# board.net
KiCad netlist of a schematic drawn in EAGLE
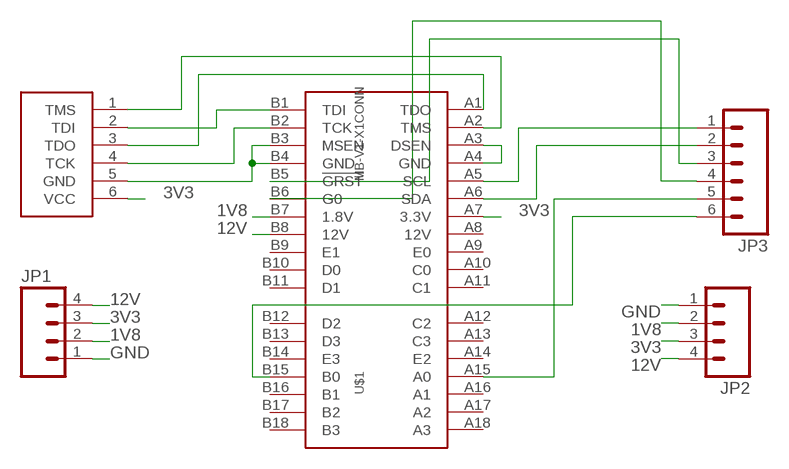
[diagram p0: schematic, sheet 1]

(export (version "E")
  (design (tool "Eeschema 10.0.6"))
  (components
    (comp (ref "JP1")
      (value "M04PTH")
      (footprint "eagle-import:1X04")
      (libsource (lib "eagle-import") (part "M04PTH"))
    )
    (comp (ref "JP2")
      (value "M04PTH")
      (footprint "eagle-import:1X04")
      (libsource (lib "eagle-import") (part "M04PTH"))
    )
    (comp (ref "JP3")
      (value "M06SIP")
      (footprint "eagle-import:1X06")
      (libsource (lib "eagle-import") (part "M06SIP"))
    )
    (comp (ref "U$1")
      (value "MB-V1-X1CONN")
      (footprint "eagle-import:PCIE-X1-CONN")
      (libsource (lib "eagle-import") (part "MB-V1-X1CONN"))
    )
    (comp (ref "U$2")
      (value "JTAGDIGILENT")
      (footprint "eagle-import:1X06")
      (libsource (lib "eagle-import") (part "JTAGDIGILENT"))
    )
  )
  (nets
    (net (code "1") (name "/1V8") (class "Default")
      (node (ref "JP1") (pin "2") (pinfunction "2_2") (pintype "passive"))
      (node (ref "JP2") (pin "2") (pinfunction "2_2") (pintype "passive"))
      (node (ref "U$1") (pin "B7") (pinfunction "1.8V_B7") (pintype "bidirectional"))
    )
    (net (code "2") (name "/3V3") (class "Default")
      (node (ref "JP1") (pin "3") (pinfunction "3_3") (pintype "passive"))
      (node (ref "JP2") (pin "3") (pinfunction "3_3") (pintype "passive"))
      (node (ref "U$1") (pin "A7") (pinfunction "3.3V_A7") (pintype "bidirectional"))
      (node (ref "U$2") (pin "6") (pinfunction "VCC_6") (pintype "bidirectional"))
    )
    (net (code "3") (name "/12V") (class "Default")
      (node (ref "JP1") (pin "4") (pinfunction "4_4") (pintype "passive"))
      (node (ref "JP2") (pin "4") (pinfunction "4_4") (pintype "passive"))
      (node (ref "U$1") (pin "B8") (pinfunction "12V_B8") (pintype "bidirectional"))
    )
    (net (code "4") (name "/GND") (class "Default")
      (node (ref "JP1") (pin "1") (pinfunction "1_1") (pintype "passive"))
      (node (ref "JP2") (pin "1") (pinfunction "1_1") (pintype "passive"))
      (node (ref "U$1") (pin "B3") (pinfunction "MSEN_B3") (pintype "bidirectional"))
      (node (ref "U$1") (pin "B4") (pinfunction "GND_B4") (pintype "bidirectional"))
      (node (ref "U$2") (pin "5") (pinfunction "GND_5") (pintype "bidirectional"))
    )
    (net (code "5") (name "Net-(U$1-A0)") (class "Default")
      (node (ref "JP3") (pin "5") (pinfunction "5_5") (pintype "passive"))
      (node (ref "U$1") (pin "A15") (pinfunction "A0_A15") (pintype "bidirectional"))
    )
    (net (code "6") (name "Net-(U$1-B0)") (class "Default")
      (node (ref "JP3") (pin "6") (pinfunction "6_6") (pintype "passive"))
      (node (ref "U$1") (pin "B15") (pinfunction "B0_B15") (pintype "bidirectional"))
    )
    (net (code "7") (name "Net-(U$1-DSEN)") (class "Default")
      (node (ref "U$1") (pin "A3") (pinfunction "DSEN_A3") (pintype "bidirectional"))
      (node (ref "U$1") (pin "A4") (pinfunction "GND_A4") (pintype "bidirectional"))
    )
    (net (code "8") (name "Net-(U$1-G0)") (class "Default")
      (node (ref "JP3") (pin "4") (pinfunction "4_4") (pintype "passive"))
      (node (ref "U$1") (pin "B6") (pinfunction "G0_B6") (pintype "bidirectional"))
    )
    (net (code "9") (name "Net-(U$1-SCL)") (class "Default")
      (node (ref "JP3") (pin "1") (pinfunction "1_1") (pintype "passive"))
      (node (ref "U$1") (pin "A5") (pinfunction "SCL_A5") (pintype "bidirectional"))
    )
    (net (code "10") (name "Net-(U$1-SDA)") (class "Default")
      (node (ref "JP3") (pin "2") (pinfunction "2_2") (pintype "passive"))
      (node (ref "U$1") (pin "A6") (pinfunction "SDA_A6") (pintype "bidirectional"))
    )
    (net (code "11") (name "Net-(U$1-TCK)") (class "Default")
      (node (ref "U$1") (pin "B2") (pinfunction "TCK_B2") (pintype "bidirectional"))
      (node (ref "U$2") (pin "4") (pinfunction "TCK_4") (pintype "bidirectional"))
    )
    (net (code "12") (name "Net-(U$1-TDI)") (class "Default")
      (node (ref "U$1") (pin "B1") (pinfunction "TDI_B1") (pintype "bidirectional"))
      (node (ref "U$2") (pin "2") (pinfunction "TDI_2") (pintype "bidirectional"))
    )
    (net (code "13") (name "Net-(U$1-TDO)") (class "Default")
      (node (ref "U$1") (pin "A1") (pinfunction "TDO_A1") (pintype "bidirectional"))
      (node (ref "U$2") (pin "3") (pinfunction "TDO_3") (pintype "bidirectional"))
    )
    (net (code "14") (name "Net-(U$1-TMS)") (class "Default")
      (node (ref "U$1") (pin "A2") (pinfunction "TMS_A2") (pintype "bidirectional"))
      (node (ref "U$2") (pin "1") (pinfunction "TMS_1") (pintype "bidirectional"))
    )
    (net (code "15") (name "Net-(U$1-~{GRST})") (class "Default")
      (node (ref "JP3") (pin "3") (pinfunction "3_3") (pintype "passive"))
      (node (ref "U$1") (pin "B5") (pinfunction "~{GRST}_B5") (pintype "bidirectional"))
    )
    (net (code "16") (name "unconnected-(U$1-12V-PadA8)") (class "Default")
      (node (ref "U$1") (pin "A8") (pinfunction "12V_A8") (pintype "bidirectional"))
    )
    (net (code "17") (name "unconnected-(U$1-A1-PadA16)") (class "Default")
      (node (ref "U$1") (pin "A16") (pinfunction "A1_A16") (pintype "bidirectional"))
    )
    (net (code "18") (name "unconnected-(U$1-A2-PadA17)") (class "Default")
      (node (ref "U$1") (pin "A17") (pinfunction "A2_A17") (pintype "bidirectional"))
    )
    (net (code "19") (name "unconnected-(U$1-A3-PadA18)") (class "Default")
      (node (ref "U$1") (pin "A18") (pinfunction "A3_A18") (pintype "bidirectional"))
    )
    (net (code "20") (name "unconnected-(U$1-B1-PadB16)") (class "Default")
      (node (ref "U$1") (pin "B16") (pinfunction "B1_B16") (pintype "bidirectional"))
    )
    (net (code "21") (name "unconnected-(U$1-B2-PadB17)") (class "Default")
      (node (ref "U$1") (pin "B17") (pinfunction "B2_B17") (pintype "bidirectional"))
    )
    (net (code "22") (name "unconnected-(U$1-B3-PadB18)") (class "Default")
      (node (ref "U$1") (pin "B18") (pinfunction "B3_B18") (pintype "bidirectional"))
    )
    (net (code "23") (name "unconnected-(U$1-C0-PadA10)") (class "Default")
      (node (ref "U$1") (pin "A10") (pinfunction "C0_A10") (pintype "bidirectional"))
    )
    (net (code "24") (name "unconnected-(U$1-C1-PadA11)") (class "Default")
      (node (ref "U$1") (pin "A11") (pinfunction "C1_A11") (pintype "bidirectional"))
    )
    (net (code "25") (name "unconnected-(U$1-C2-PadA12)") (class "Default")
      (node (ref "U$1") (pin "A12") (pinfunction "C2_A12") (pintype "bidirectional"))
    )
    (net (code "26") (name "unconnected-(U$1-C3-PadA13)") (class "Default")
      (node (ref "U$1") (pin "A13") (pinfunction "C3_A13") (pintype "bidirectional"))
    )
    (net (code "27") (name "unconnected-(U$1-D0-PadB10)") (class "Default")
      (node (ref "U$1") (pin "B10") (pinfunction "D0_B10") (pintype "bidirectional"))
    )
    (net (code "28") (name "unconnected-(U$1-D1-PadB11)") (class "Default")
      (node (ref "U$1") (pin "B11") (pinfunction "D1_B11") (pintype "bidirectional"))
    )
    (net (code "29") (name "unconnected-(U$1-D2-PadB12)") (class "Default")
      (node (ref "U$1") (pin "B12") (pinfunction "D2_B12") (pintype "bidirectional"))
    )
    (net (code "30") (name "unconnected-(U$1-D3-PadB13)") (class "Default")
      (node (ref "U$1") (pin "B13") (pinfunction "D3_B13") (pintype "bidirectional"))
    )
    (net (code "31") (name "unconnected-(U$1-E0-PadA9)") (class "Default")
      (node (ref "U$1") (pin "A9") (pinfunction "E0_A9") (pintype "bidirectional"))
    )
    (net (code "32") (name "unconnected-(U$1-E1-PadB9)") (class "Default")
      (node (ref "U$1") (pin "B9") (pinfunction "E1_B9") (pintype "bidirectional"))
    )
    (net (code "33") (name "unconnected-(U$1-E2-PadA14)") (class "Default")
      (node (ref "U$1") (pin "A14") (pinfunction "E2_A14") (pintype "bidirectional"))
    )
    (net (code "34") (name "unconnected-(U$1-E3-PadB14)") (class "Default")
      (node (ref "U$1") (pin "B14") (pinfunction "E3_B14") (pintype "bidirectional"))
    )
  )
)
